# paris_relay_rev_B.net
KiCad netlist of a schematic drawn in EAGLE
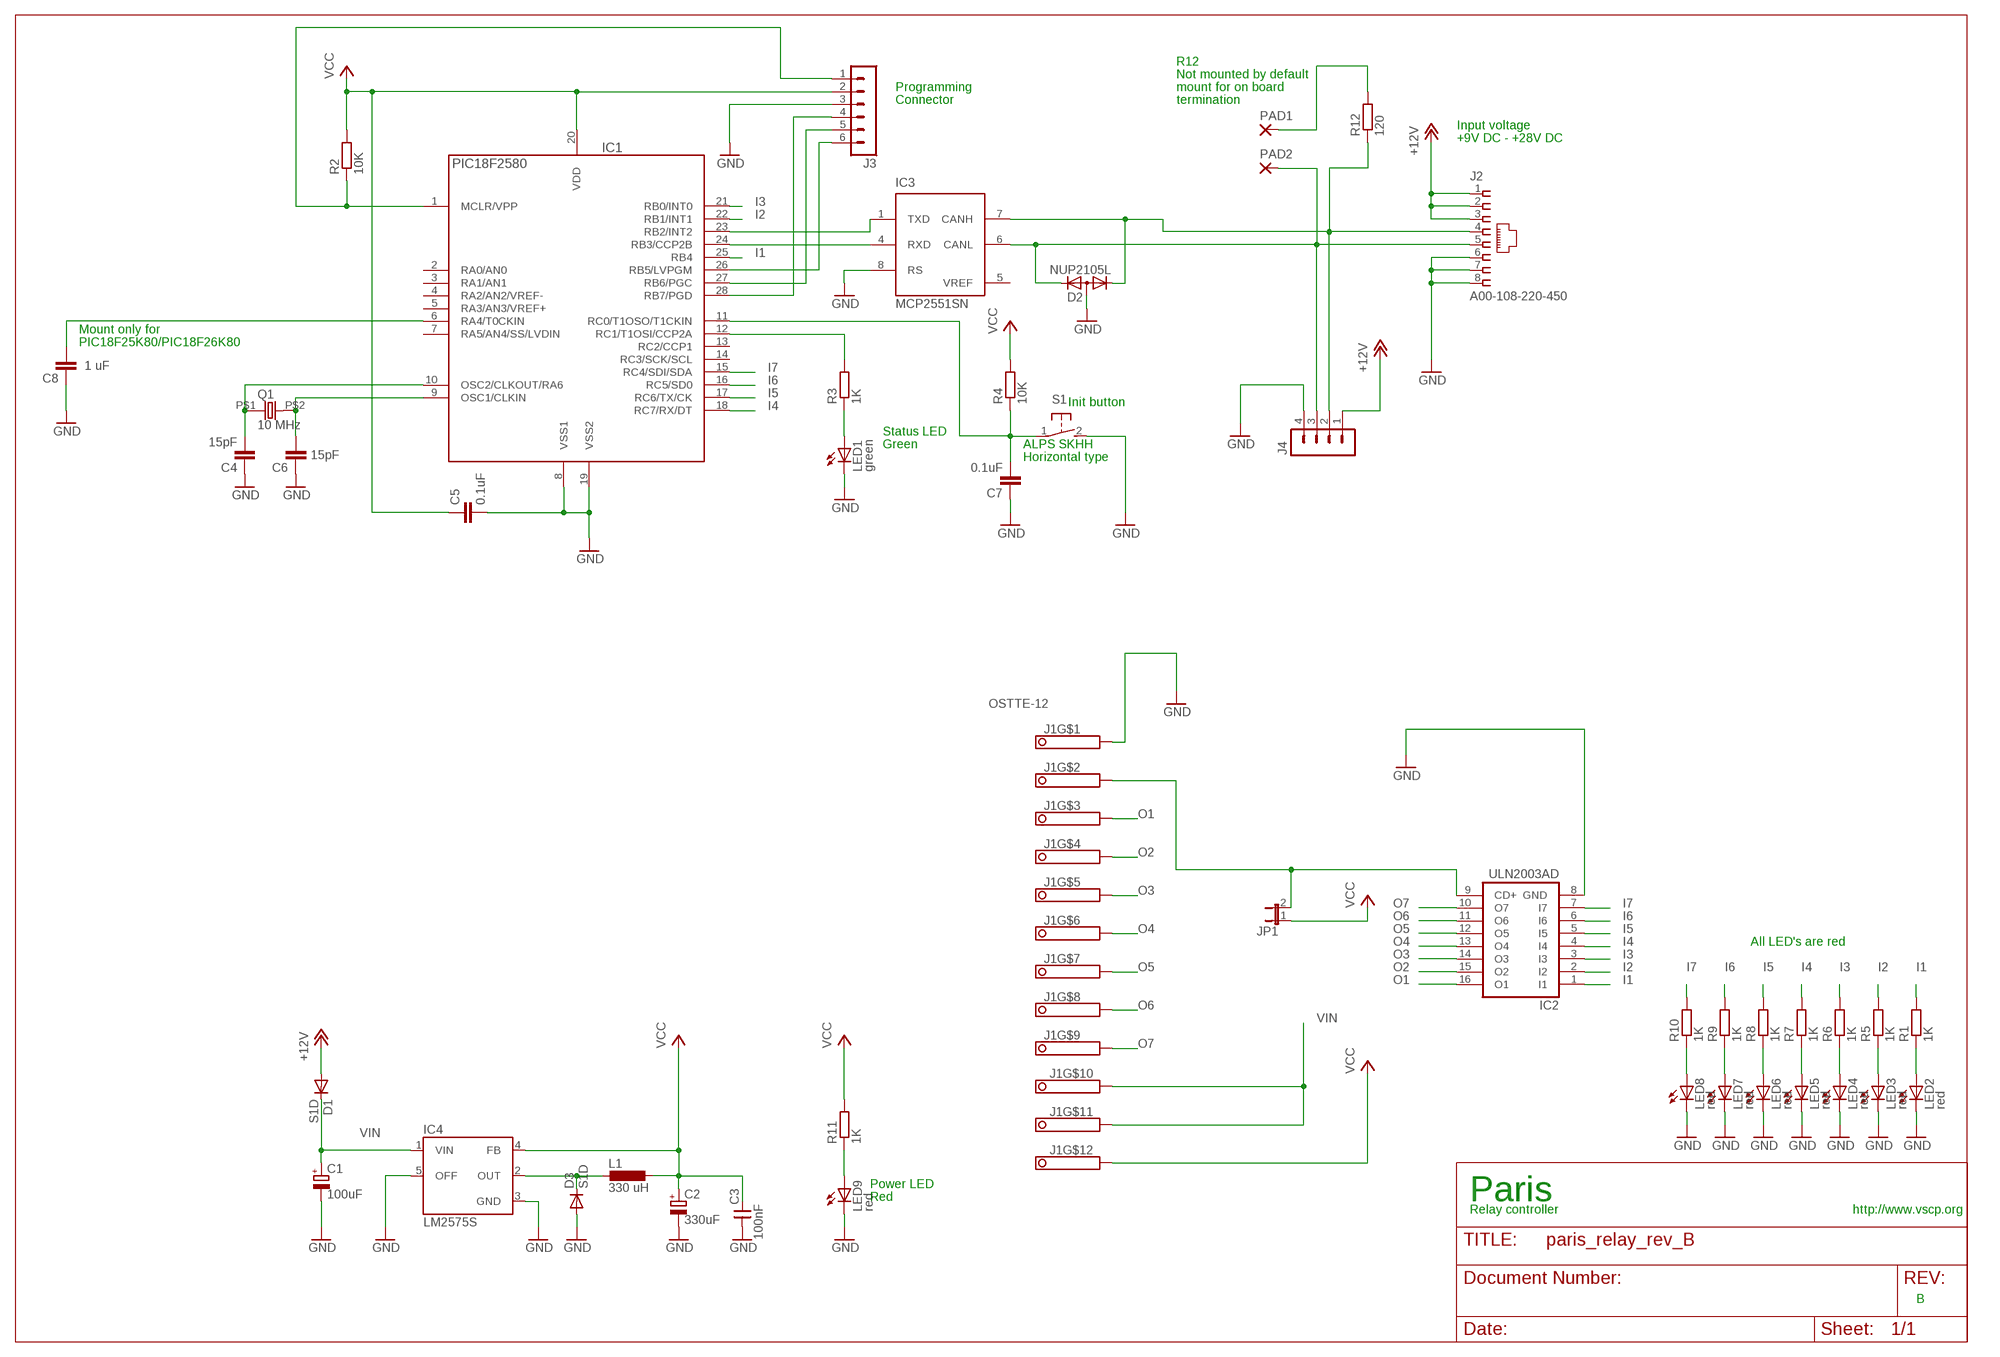
[diagram p0: schematic, sheet 1]

(export (version "E")
  (design (tool "Eeschema 10.0.6"))
  (components
    (comp (ref "C1")
      (value "100uF")
      (footprint "eagle-import:PANASONIC_D")
      (libsource (lib "eagle-import") (part "CPOL-EUD"))
    )
    (comp (ref "C2")
      (value "330uF")
      (footprint "eagle-import:PANASONIC_D")
      (libsource (lib "eagle-import") (part "CPOL-EUD"))
    )
    (comp (ref "C3")
      (value "100nF")
      (footprint "eagle-import:0805")
      (libsource (lib "eagle-import") (part "CNP-0805"))
    )
    (comp (ref "C4")
      (value "15pF")
      (footprint "eagle-import:C0805")
      (libsource (lib "eagle-import") (part "C-EUC0805"))
    )
    (comp (ref "C5")
      (value "0.1uF")
      (footprint "eagle-import:C0805")
      (libsource (lib "eagle-import") (part "C-EUC0805"))
    )
    (comp (ref "C6")
      (value "15pF")
      (footprint "eagle-import:C0805")
      (libsource (lib "eagle-import") (part "C-EUC0805"))
    )
    (comp (ref "C7")
      (value "0.1uF")
      (footprint "eagle-import:C0805")
      (libsource (lib "eagle-import") (part "C-EUC0805"))
    )
    (comp (ref "C8")
      (value "1 uF")
      (footprint "eagle-import:C0805")
      (libsource (lib "eagle-import") (part "C-EUC0805"))
    )
    (comp (ref "D1")
      (value "S1D")
      (footprint "eagle-import:SOD123")
      (libsource (lib "eagle-import") (part "DIODE-SOD123"))
    )
    (comp (ref "D2")
      (value "NUP2105L")
      (footprint "eagle-import:SOT23")
      (libsource (lib "eagle-import") (part "DIODE-2CA|ACSOT23"))
    )
    (comp (ref "D3")
      (value "S1D")
      (footprint "eagle-import:SOD123")
      (libsource (lib "eagle-import") (part "DIODE-SOD123"))
    )
    (comp (ref "IC1")
      (value "PIC18F2580")
      (footprint "eagle-import:SO28")
      (libsource (lib "eagle-import") (part "PIC18F252-?I/SOL"))
    )
    (comp (ref "IC2")
      (value "ULN2003AD")
      (footprint "eagle-import:SO16")
      (libsource (lib "eagle-import") (part "ULN2003AD"))
    )
    (comp (ref "IC3")
      (value "MCP2551SN")
      (footprint "eagle-import:SO-08")
      (libsource (lib "eagle-import") (part "MCP2551SN"))
    )
    (comp (ref "IC4")
      (value "LM2575S")
      (footprint "eagle-import:TO263-5")
      (libsource (lib "eagle-import") (part "LM2575S"))
    )
    (comp (ref "J1")
      (value "OSTTE-12")
      (footprint "eagle-import:PINHEAD-12")
      (libsource (lib "eagle-import") (part "OSTTE-12"))
    )
    (comp (ref "J2")
      (value "A00-108-220-450")
      (footprint "eagle-import:RJ-45")
      (libsource (lib "eagle-import") (part "A00-108-220-450"))
    )
    (comp (ref "J3")
      (value "MA06-1")
      (footprint "eagle-import:MA06-1")
      (libsource (lib "eagle-import") (part "MA06-1"))
    )
    (comp (ref "J4")
      (value "MA04-1")
      (footprint "eagle-import:MA04-1")
      (libsource (lib "eagle-import") (part "MA04-1"))
    )
    (comp (ref "JP1")
      (value "JP1E")
      (footprint "eagle-import:JP1")
      (libsource (lib "eagle-import") (part "JP1E"))
    )
    (comp (ref "L1")
      (value "330 uH")
      (footprint "eagle-import:DO3316P")
      (libsource (lib "eagle-import") (part "DO3316P"))
    )
    (comp (ref "LED1")
      (value "green")
      (footprint "eagle-import:CHIP-LED0805")
      (libsource (lib "eagle-import") (part "LEDCHIP-LED0805"))
    )
    (comp (ref "LED2")
      (value "red")
      (footprint "eagle-import:CHIP-LED0805")
      (libsource (lib "eagle-import") (part "LEDCHIP-LED0805"))
    )
    (comp (ref "LED3")
      (value "red")
      (footprint "eagle-import:CHIP-LED0805")
      (libsource (lib "eagle-import") (part "LEDCHIP-LED0805"))
    )
    (comp (ref "LED4")
      (value "red")
      (footprint "eagle-import:CHIP-LED0805")
      (libsource (lib "eagle-import") (part "LEDCHIP-LED0805"))
    )
    (comp (ref "LED5")
      (value "red")
      (footprint "eagle-import:CHIP-LED0805")
      (libsource (lib "eagle-import") (part "LEDCHIP-LED0805"))
    )
    (comp (ref "LED6")
      (value "red")
      (footprint "eagle-import:CHIP-LED0805")
      (libsource (lib "eagle-import") (part "LEDCHIP-LED0805"))
    )
    (comp (ref "LED7")
      (value "red")
      (footprint "eagle-import:CHIP-LED0805")
      (libsource (lib "eagle-import") (part "LEDCHIP-LED0805"))
    )
    (comp (ref "LED8")
      (value "red")
      (footprint "eagle-import:CHIP-LED0805")
      (libsource (lib "eagle-import") (part "LEDCHIP-LED0805"))
    )
    (comp (ref "LED9")
      (value "red")
      (footprint "eagle-import:CHIP-LED0805")
      (libsource (lib "eagle-import") (part "LEDCHIP-LED0805"))
    )
    (comp (ref "PAD1")
      (value "1,6/0,8")
      (footprint "eagle-import:1,6_0,8")
      (libsource (lib "eagle-import") (part "1,6/0,8"))
    )
    (comp (ref "PAD2")
      (value "1,6/0,8")
      (footprint "eagle-import:1,6_0,8")
      (libsource (lib "eagle-import") (part "1,6/0,8"))
    )
    (comp (ref "Q1")
      (value "10 MHz")
      (footprint "eagle-import:9C")
      (libsource (lib "eagle-import") (part "HC-49S"))
    )
    (comp (ref "R1")
      (value "1K")
      (footprint "eagle-import:R0805")
      (libsource (lib "eagle-import") (part "R-EU_R0805"))
    )
    (comp (ref "R2")
      (value "10K")
      (footprint "eagle-import:R0805")
      (libsource (lib "eagle-import") (part "R-EU_R0805"))
    )
    (comp (ref "R3")
      (value "1K")
      (footprint "eagle-import:R0805")
      (libsource (lib "eagle-import") (part "R-EU_R0805"))
    )
    (comp (ref "R4")
      (value "10K")
      (footprint "eagle-import:R0805")
      (libsource (lib "eagle-import") (part "R-EU_R0805"))
    )
    (comp (ref "R5")
      (value "1K")
      (footprint "eagle-import:R0805")
      (libsource (lib "eagle-import") (part "R-EU_R0805"))
    )
    (comp (ref "R6")
      (value "1K")
      (footprint "eagle-import:R0805")
      (libsource (lib "eagle-import") (part "R-EU_R0805"))
    )
    (comp (ref "R7")
      (value "1K")
      (footprint "eagle-import:R0805")
      (libsource (lib "eagle-import") (part "R-EU_R0805"))
    )
    (comp (ref "R8")
      (value "1K")
      (footprint "eagle-import:R0805")
      (libsource (lib "eagle-import") (part "R-EU_R0805"))
    )
    (comp (ref "R9")
      (value "1K")
      (footprint "eagle-import:R0805")
      (libsource (lib "eagle-import") (part "R-EU_R0805"))
    )
    (comp (ref "R10")
      (value "1K")
      (footprint "eagle-import:R0805")
      (libsource (lib "eagle-import") (part "R-EU_R0805"))
    )
    (comp (ref "R11")
      (value "1K")
      (footprint "eagle-import:R0805")
      (libsource (lib "eagle-import") (part "R-EU_R0805"))
    )
    (comp (ref "R12")
      (value "120")
      (footprint "eagle-import:R0805")
      (libsource (lib "eagle-import") (part "R-EU_R0805"))
    )
    (comp (ref "S1")
      (value "31-XX")
      (footprint "eagle-import:B3F-31XX")
      (fields (field (name "MPN") "B3F-3100"))
      (libsource (lib "eagle-import") (part "31-XX"))
    )
  )
  (nets
    (net (code "1") (name "+12V") (class "Default")
      (node (ref "D1") (pin "A") (pinfunction "A_A") (pintype "passive"))
      (node (ref "J2") (pin "1") (pinfunction "1_1") (pintype "passive"))
      (node (ref "J2") (pin "2") (pinfunction "2_2") (pintype "passive"))
      (node (ref "J2") (pin "3") (pinfunction "3_3") (pintype "passive"))
      (node (ref "J4") (pin "1") (pinfunction "1_1") (pintype "passive"))
    )
    (net (code "2") (name "/I1") (class "Default")
      (node (ref "IC1") (pin "25") (pinfunction "RB4_25") (pintype "bidirectional"))
      (node (ref "IC2") (pin "1") (pinfunction "I1_1") (pintype "input"))
      (node (ref "R1") (pin "2") (pinfunction "2_2") (pintype "passive"))
    )
    (net (code "3") (name "/I2") (class "Default")
      (node (ref "IC1") (pin "22") (pinfunction "RB1/INT1_22") (pintype "bidirectional"))
      (node (ref "IC2") (pin "2") (pinfunction "I2_2") (pintype "input"))
      (node (ref "R5") (pin "2") (pinfunction "2_2") (pintype "passive"))
    )
    (net (code "4") (name "/I3") (class "Default")
      (node (ref "IC1") (pin "21") (pinfunction "RB0/INT0_21") (pintype "bidirectional"))
      (node (ref "IC2") (pin "3") (pinfunction "I3_3") (pintype "input"))
      (node (ref "R6") (pin "2") (pinfunction "2_2") (pintype "passive"))
    )
    (net (code "5") (name "/I4") (class "Default")
      (node (ref "IC1") (pin "18") (pinfunction "RC7/RX/DT_18") (pintype "bidirectional"))
      (node (ref "IC2") (pin "4") (pinfunction "I4_4") (pintype "input"))
      (node (ref "R7") (pin "2") (pinfunction "2_2") (pintype "passive"))
    )
    (net (code "6") (name "/I5") (class "Default")
      (node (ref "IC1") (pin "17") (pinfunction "RC6/TX/CK_17") (pintype "bidirectional"))
      (node (ref "IC2") (pin "5") (pinfunction "I5_5") (pintype "input"))
      (node (ref "R8") (pin "2") (pinfunction "2_2") (pintype "passive"))
    )
    (net (code "7") (name "/I6") (class "Default")
      (node (ref "IC1") (pin "16") (pinfunction "RC5/SD0_16") (pintype "bidirectional"))
      (node (ref "IC2") (pin "6") (pinfunction "I6_6") (pintype "input"))
      (node (ref "R9") (pin "2") (pinfunction "2_2") (pintype "passive"))
    )
    (net (code "8") (name "/I7") (class "Default")
      (node (ref "IC1") (pin "15") (pinfunction "RC4/SDI/SDA_15") (pintype "bidirectional"))
      (node (ref "IC2") (pin "7") (pinfunction "I7_7") (pintype "input"))
      (node (ref "R10") (pin "2") (pinfunction "2_2") (pintype "passive"))
    )
    (net (code "9") (name "/O1") (class "Default")
      (node (ref "IC2") (pin "16") (pinfunction "O1_16") (pintype "open_collector"))
      (node (ref "J1") (pin "3") (pinfunction "K_3") (pintype "passive"))
    )
    (net (code "10") (name "/O2") (class "Default")
      (node (ref "IC2") (pin "15") (pinfunction "O2_15") (pintype "open_collector"))
      (node (ref "J1") (pin "4") (pinfunction "K_4") (pintype "passive"))
    )
    (net (code "11") (name "/O3") (class "Default")
      (node (ref "IC2") (pin "14") (pinfunction "O3_14") (pintype "open_collector"))
      (node (ref "J1") (pin "5") (pinfunction "K_5") (pintype "passive"))
    )
    (net (code "12") (name "/O4") (class "Default")
      (node (ref "IC2") (pin "13") (pinfunction "O4_13") (pintype "open_collector"))
      (node (ref "J1") (pin "6") (pinfunction "K_6") (pintype "passive"))
    )
    (net (code "13") (name "/O5") (class "Default")
      (node (ref "IC2") (pin "12") (pinfunction "O5_12") (pintype "open_collector"))
      (node (ref "J1") (pin "7") (pinfunction "K_7") (pintype "passive"))
    )
    (net (code "14") (name "/O6") (class "Default")
      (node (ref "IC2") (pin "11") (pinfunction "O6_11") (pintype "open_collector"))
      (node (ref "J1") (pin "8") (pinfunction "K_8") (pintype "passive"))
    )
    (net (code "15") (name "/O7") (class "Default")
      (node (ref "IC2") (pin "10") (pinfunction "O7_10") (pintype "open_collector"))
      (node (ref "J1") (pin "9") (pinfunction "K_9") (pintype "passive"))
    )
    (net (code "16") (name "/VIN") (class "Default")
      (node (ref "C1") (pin "+") (pinfunction "+_+") (pintype "passive"))
      (node (ref "D1") (pin "C") (pinfunction "C_C") (pintype "passive"))
      (node (ref "IC4") (pin "1") (pinfunction "VIN_1") (pintype "power_in"))
      (node (ref "J1") (pin "10") (pinfunction "K_10") (pintype "passive"))
      (node (ref "J1") (pin "11") (pinfunction "K_11") (pintype "passive"))
    )
    (net (code "17") (name "/VREF") (class "Default")
      (node (ref "IC3") (pin "5") (pinfunction "VREF_5") (pintype "power_in"))
    )
    (net (code "18") (name "GND") (class "Default")
      (node (ref "C1") (pin "-") (pinfunction "-_-") (pintype "passive"))
      (node (ref "C2") (pin "-") (pinfunction "-_-") (pintype "passive"))
      (node (ref "C3") (pin "1") (pinfunction "1_1") (pintype "passive"))
      (node (ref "C4") (pin "1") (pinfunction "1_1") (pintype "passive"))
      (node (ref "C5") (pin "2") (pinfunction "2_2") (pintype "passive"))
      (node (ref "C6") (pin "1") (pinfunction "1_1") (pintype "passive"))
      (node (ref "C7") (pin "1") (pinfunction "1_1") (pintype "passive"))
      (node (ref "C8") (pin "1") (pinfunction "1_1") (pintype "passive"))
      (node (ref "D2") (pin "3") (pinfunction "A_3") (pintype "passive"))
      (node (ref "D3") (pin "A") (pinfunction "A_A") (pintype "passive"))
      (node (ref "IC1") (pin "19") (pinfunction "VSS2_19") (pintype "power_in"))
      (node (ref "IC1") (pin "8") (pinfunction "VSS1_8") (pintype "power_in"))
      (node (ref "IC2") (pin "8") (pinfunction "GND_8") (pintype "power_in"))
      (node (ref "IC3") (pin "8") (pinfunction "RS_8") (pintype "input"))
      (node (ref "IC4") (pin "3") (pinfunction "GND_3") (pintype "power_in"))
      (node (ref "IC4") (pin "5") (pinfunction "OFF_5") (pintype "input"))
      (node (ref "J1") (pin "1") (pinfunction "K_1") (pintype "passive"))
      (node (ref "J2") (pin "6") (pinfunction "6_6") (pintype "passive"))
      (node (ref "J2") (pin "7") (pinfunction "7_7") (pintype "passive"))
      (node (ref "J2") (pin "8") (pinfunction "8_8") (pintype "passive"))
      (node (ref "J3") (pin "3") (pinfunction "3_3") (pintype "passive"))
      (node (ref "J4") (pin "4") (pinfunction "4_4") (pintype "passive"))
      (node (ref "LED1") (pin "C") (pinfunction "C_C") (pintype "passive"))
      (node (ref "LED2") (pin "C") (pinfunction "C_C") (pintype "passive"))
      (node (ref "LED3") (pin "C") (pinfunction "C_C") (pintype "passive"))
      (node (ref "LED4") (pin "C") (pinfunction "C_C") (pintype "passive"))
      (node (ref "LED5") (pin "C") (pinfunction "C_C") (pintype "passive"))
      (node (ref "LED6") (pin "C") (pinfunction "C_C") (pintype "passive"))
      (node (ref "LED7") (pin "C") (pinfunction "C_C") (pintype "passive"))
      (node (ref "LED8") (pin "C") (pinfunction "C_C") (pintype "passive"))
      (node (ref "LED9") (pin "C") (pinfunction "C_C") (pintype "passive"))
      (node (ref "S1") (pin "2") (pinfunction "S_2") (pintype "passive"))
    )
    (net (code "19") (name "Net-(D2-K1)") (class "Default")
      (node (ref "D2") (pin "1") (pinfunction "K1_1") (pintype "passive"))
      (node (ref "IC3") (pin "7") (pinfunction "CANH_7") (pintype "bidirectional"))
      (node (ref "J2") (pin "4") (pinfunction "4_4") (pintype "passive"))
      (node (ref "J4") (pin "2") (pinfunction "2_2") (pintype "passive"))
      (node (ref "R12") (pin "1") (pinfunction "1_1") (pintype "passive"))
    )
    (net (code "20") (name "Net-(D2-K2)") (class "Default")
      (node (ref "D2") (pin "2") (pinfunction "K2_2") (pintype "passive"))
      (node (ref "IC3") (pin "6") (pinfunction "CANL_6") (pintype "bidirectional"))
      (node (ref "J2") (pin "5") (pinfunction "5_5") (pintype "passive"))
      (node (ref "J4") (pin "3") (pinfunction "3_3") (pintype "passive"))
      (node (ref "PAD2") (pin "1") (pinfunction "P_1") (pintype "passive"))
    )
    (net (code "21") (name "Net-(IC1-MCLR{slash}VPP)") (class "Default")
      (node (ref "IC1") (pin "1") (pinfunction "MCLR/VPP_1") (pintype "input"))
      (node (ref "J3") (pin "1") (pinfunction "1_1") (pintype "passive"))
      (node (ref "R2") (pin "1") (pinfunction "1_1") (pintype "passive"))
    )
    (net (code "22") (name "Net-(IC1-OSC1{slash}CLKIN)") (class "Default")
      (node (ref "C6") (pin "2") (pinfunction "2_2") (pintype "passive"))
      (node (ref "IC1") (pin "9") (pinfunction "OSC1/CLKIN_9") (pintype "input"))
      (node (ref "Q1") (pin "P$2") (pinfunction "2_P$2") (pintype "passive"))
    )
    (net (code "23") (name "Net-(IC1-OSC2{slash}CLKOUT{slash}RA6)") (class "Default")
      (node (ref "C4") (pin "2") (pinfunction "2_2") (pintype "passive"))
      (node (ref "IC1") (pin "10") (pinfunction "OSC2/CLKOUT/RA6_10") (pintype "output"))
      (node (ref "Q1") (pin "P$1") (pinfunction "1_P$1") (pintype "passive"))
    )
    (net (code "24") (name "Net-(IC1-RA4{slash}T0CKIN)") (class "Default")
      (node (ref "C8") (pin "2") (pinfunction "2_2") (pintype "passive"))
      (node (ref "IC1") (pin "6") (pinfunction "RA4/T0CKIN_6") (pintype "open_collector"))
    )
    (net (code "25") (name "Net-(IC1-RB2{slash}INT2)") (class "Default")
      (node (ref "IC1") (pin "23") (pinfunction "RB2/INT2_23") (pintype "bidirectional"))
      (node (ref "IC3") (pin "1") (pinfunction "TXD_1") (pintype "input"))
    )
    (net (code "26") (name "Net-(IC1-RB3{slash}CCP2B)") (class "Default")
      (node (ref "IC1") (pin "24") (pinfunction "RB3/CCP2B_24") (pintype "bidirectional"))
      (node (ref "IC3") (pin "4") (pinfunction "RXD_4") (pintype "output"))
    )
    (net (code "27") (name "Net-(IC1-RB5{slash}LVPGM)") (class "Default")
      (node (ref "IC1") (pin "26") (pinfunction "RB5/LVPGM_26") (pintype "bidirectional"))
      (node (ref "J3") (pin "6") (pinfunction "6_6") (pintype "passive"))
    )
    (net (code "28") (name "Net-(IC1-RB6{slash}PGC)") (class "Default")
      (node (ref "IC1") (pin "27") (pinfunction "RB6/PGC_27") (pintype "bidirectional"))
      (node (ref "J3") (pin "5") (pinfunction "5_5") (pintype "passive"))
    )
    (net (code "29") (name "Net-(IC1-RB7{slash}PGD)") (class "Default")
      (node (ref "IC1") (pin "28") (pinfunction "RB7/PGD_28") (pintype "bidirectional"))
      (node (ref "J3") (pin "4") (pinfunction "4_4") (pintype "passive"))
    )
    (net (code "30") (name "Net-(IC1-RC0{slash}T1OSO{slash}T1CKIN)") (class "Default")
      (node (ref "C7") (pin "2") (pinfunction "2_2") (pintype "passive"))
      (node (ref "IC1") (pin "11") (pinfunction "RC0/T1OSO/T1CKIN_11") (pintype "bidirectional"))
      (node (ref "R4") (pin "1") (pinfunction "1_1") (pintype "passive"))
      (node (ref "S1") (pin "1") (pinfunction "P_1") (pintype "passive"))
    )
    (net (code "31") (name "Net-(IC1-RC1{slash}T1OSI{slash}CCP2A)") (class "Default")
      (node (ref "IC1") (pin "12") (pinfunction "RC1/T1OSI/CCP2A_12") (pintype "bidirectional"))
      (node (ref "R3") (pin "2") (pinfunction "2_2") (pintype "passive"))
    )
    (net (code "32") (name "Net-(IC2-CD+)") (class "Default")
      (node (ref "IC2") (pin "9") (pinfunction "CD+_9") (pintype "passive"))
      (node (ref "J1") (pin "2") (pinfunction "K_2") (pintype "passive"))
      (node (ref "JP1") (pin "2") (pinfunction "2_2") (pintype "passive"))
    )
    (net (code "33") (name "Net-(IC4-OUT)") (class "Default")
      (node (ref "D3") (pin "C") (pinfunction "C_C") (pintype "passive"))
      (node (ref "IC4") (pin "2") (pinfunction "OUT_2") (pintype "output"))
      (node (ref "L1") (pin "1") (pinfunction "1_1") (pintype "passive"))
    )
    (net (code "34") (name "Net-(LED1-PadA)") (class "Default")
      (node (ref "LED1") (pin "A") (pinfunction "A_A") (pintype "passive"))
      (node (ref "R3") (pin "1") (pinfunction "1_1") (pintype "passive"))
    )
    (net (code "35") (name "Net-(LED2-PadA)") (class "Default")
      (node (ref "LED2") (pin "A") (pinfunction "A_A") (pintype "passive"))
      (node (ref "R1") (pin "1") (pinfunction "1_1") (pintype "passive"))
    )
    (net (code "36") (name "Net-(LED3-PadA)") (class "Default")
      (node (ref "LED3") (pin "A") (pinfunction "A_A") (pintype "passive"))
      (node (ref "R5") (pin "1") (pinfunction "1_1") (pintype "passive"))
    )
    (net (code "37") (name "Net-(LED4-PadA)") (class "Default")
      (node (ref "LED4") (pin "A") (pinfunction "A_A") (pintype "passive"))
      (node (ref "R6") (pin "1") (pinfunction "1_1") (pintype "passive"))
    )
    (net (code "38") (name "Net-(LED5-PadA)") (class "Default")
      (node (ref "LED5") (pin "A") (pinfunction "A_A") (pintype "passive"))
      (node (ref "R7") (pin "1") (pinfunction "1_1") (pintype "passive"))
    )
    (net (code "39") (name "Net-(LED6-PadA)") (class "Default")
      (node (ref "LED6") (pin "A") (pinfunction "A_A") (pintype "passive"))
      (node (ref "R8") (pin "1") (pinfunction "1_1") (pintype "passive"))
    )
    (net (code "40") (name "Net-(LED7-PadA)") (class "Default")
      (node (ref "LED7") (pin "A") (pinfunction "A_A") (pintype "passive"))
      (node (ref "R9") (pin "1") (pinfunction "1_1") (pintype "passive"))
    )
    (net (code "41") (name "Net-(LED8-PadA)") (class "Default")
      (node (ref "LED8") (pin "A") (pinfunction "A_A") (pintype "passive"))
      (node (ref "R10") (pin "1") (pinfunction "1_1") (pintype "passive"))
    )
    (net (code "42") (name "Net-(LED9-PadA)") (class "Default")
      (node (ref "LED9") (pin "A") (pinfunction "A_A") (pintype "passive"))
      (node (ref "R11") (pin "1") (pinfunction "1_1") (pintype "passive"))
    )
    (net (code "43") (name "Net-(PAD1-P)") (class "Default")
      (node (ref "PAD1") (pin "1") (pinfunction "P_1") (pintype "passive"))
      (node (ref "R12") (pin "2") (pinfunction "2_2") (pintype "passive"))
    )
    (net (code "44") (name "VCC") (class "Default")
      (node (ref "C2") (pin "+") (pinfunction "+_+") (pintype "passive"))
      (node (ref "C3") (pin "2") (pinfunction "2_2") (pintype "passive"))
      (node (ref "C5") (pin "1") (pinfunction "1_1") (pintype "passive"))
      (node (ref "IC1") (pin "20") (pinfunction "VDD_20") (pintype "power_in"))
      (node (ref "IC4") (pin "4") (pinfunction "FB_4") (pintype "input"))
      (node (ref "J1") (pin "12") (pinfunction "K_12") (pintype "passive"))
      (node (ref "J3") (pin "2") (pinfunction "2_2") (pintype "passive"))
      (node (ref "JP1") (pin "1") (pinfunction "1_1") (pintype "passive"))
      (node (ref "L1") (pin "2") (pinfunction "2_2") (pintype "passive"))
      (node (ref "R11") (pin "2") (pinfunction "2_2") (pintype "passive"))
      (node (ref "R2") (pin "2") (pinfunction "2_2") (pintype "passive"))
      (node (ref "R4") (pin "2") (pinfunction "2_2") (pintype "passive"))
    )
    (net (code "45") (name "unconnected-(IC1-RA0{slash}AN0-Pad2)") (class "Default")
      (node (ref "IC1") (pin "2") (pinfunction "RA0/AN0_2") (pintype "bidirectional"))
    )
    (net (code "46") (name "unconnected-(IC1-RA1{slash}AN1-Pad3)") (class "Default")
      (node (ref "IC1") (pin "3") (pinfunction "RA1/AN1_3") (pintype "bidirectional"))
    )
    (net (code "47") (name "unconnected-(IC1-RA2{slash}AN2{slash}VREF--Pad4)") (class "Default")
      (node (ref "IC1") (pin "4") (pinfunction "RA2/AN2/VREF-_4") (pintype "bidirectional"))
    )
    (net (code "48") (name "unconnected-(IC1-RA3{slash}AN3{slash}VREF+-Pad5)") (class "Default")
      (node (ref "IC1") (pin "5") (pinfunction "RA3/AN3/VREF+_5") (pintype "bidirectional"))
    )
    (net (code "49") (name "unconnected-(IC1-RA5{slash}AN4{slash}SS{slash}LVDIN-Pad7)") (class "Default")
      (node (ref "IC1") (pin "7") (pinfunction "RA5/AN4/SS/LVDIN_7") (pintype "bidirectional"))
    )
    (net (code "50") (name "unconnected-(IC1-RC2{slash}CCP1-Pad13)") (class "Default")
      (node (ref "IC1") (pin "13") (pinfunction "RC2/CCP1_13") (pintype "bidirectional"))
    )
    (net (code "51") (name "unconnected-(IC1-RC3{slash}SCK{slash}SCL-Pad14)") (class "Default")
      (node (ref "IC1") (pin "14") (pinfunction "RC3/SCK/SCL_14") (pintype "bidirectional"))
    )
  )
)
